# tritiled_v30_oslon.net
KiCad netlist of a schematic drawn in EAGLE
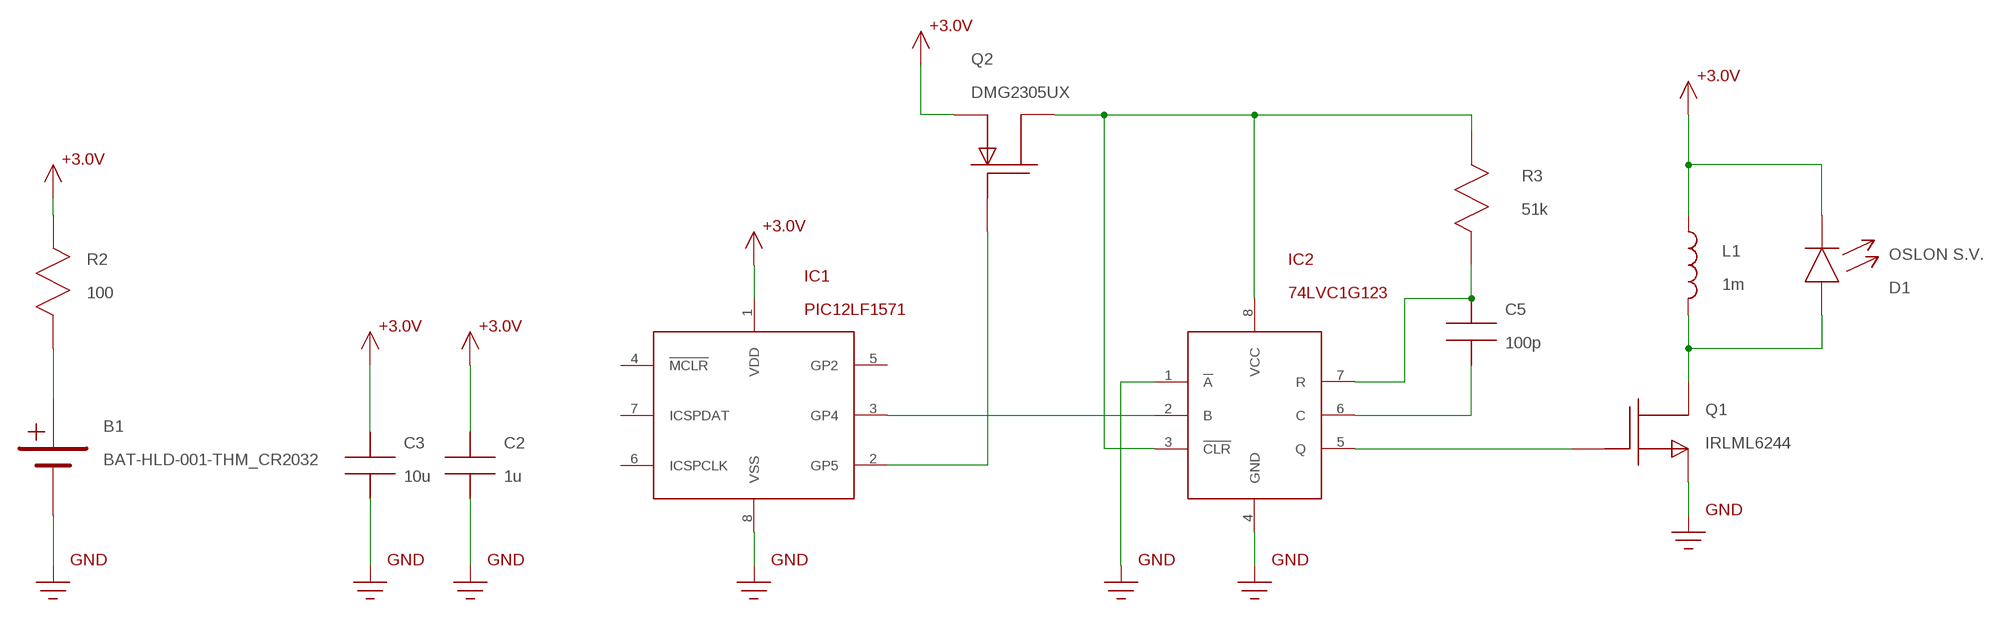
[diagram p0: schematic, sheet 1]

(export (version "E")
  (design (tool "Eeschema 10.0.6"))
  (components
    (comp (ref "B1")
      (value "BAT-HLD-001-THM_CR2032")
      (footprint "eagle-import:CR2032_BAT-HLD-001-THM")
      (libsource (lib "eagle-import") (part "BAT-HLD-001-THM_CR2032"))
    )
    (comp (ref "C2")
      (value "1u")
      (footprint "eagle-import:0805")
      (libsource (lib "eagle-import") (part "C0805"))
    )
    (comp (ref "C3")
      (value "10u")
      (footprint "eagle-import:1206")
      (libsource (lib "eagle-import") (part "C1206"))
    )
    (comp (ref "C5")
      (value "100p")
      (footprint "eagle-import:C0603")
      (libsource (lib "eagle-import") (part "C0603"))
    )
    (comp (ref "D1")
      (value "OSLON S.V.")
      (footprint "eagle-import:OSLON_3030_LED")
      (libsource (lib "eagle-import") (part "OSLON_SIGNAL"))
    )
    (comp (ref "IC1")
      (value "PIC12LF1571")
      (footprint "eagle-import:SOIC8")
      (libsource (lib "eagle-import") (part "PIC12LF1571"))
    )
    (comp (ref "IC2")
      (value "74LVC1G123")
      (footprint "eagle-import:SM8")
      (libsource (lib "eagle-import") (part "74LVC1G123"))
    )
    (comp (ref "L1")
      (value "1m")
      (footprint "eagle-import:SRR6028_INDUCTOR")
      (libsource (lib "eagle-import") (part "SRR6028_INDUCTOR"))
    )
    (comp (ref "Q1")
      (value "IRLML6244")
      (footprint "eagle-import:SOT-23")
      (libsource (lib "eagle-import") (part "ZXMN3B01FSOT23"))
    )
    (comp (ref "Q2")
      (value "DMG2305UX")
      (footprint "eagle-import:SOT-23")
      (libsource (lib "eagle-import") (part "DMG2305UXSOT23"))
    )
    (comp (ref "R2")
      (value "100")
      (footprint "eagle-import:R1206")
      (libsource (lib "eagle-import") (part "R1206"))
    )
    (comp (ref "R3")
      (value "51k")
      (footprint "eagle-import:R0603")
      (libsource (lib "eagle-import") (part "R0603"))
    )
  )
  (nets
    (net (code "1") (name "+3.0V") (class "Default")
      (node (ref "C2") (pin "P$1") (pinfunction "P$1_P$1") (pintype "bidirectional"))
      (node (ref "C3") (pin "P$1") (pinfunction "P$1_P$1") (pintype "bidirectional"))
      (node (ref "D1") (pin "C") (pinfunction "C_C") (pintype "bidirectional"))
      (node (ref "IC1") (pin "1") (pinfunction "VDD_1") (pintype "bidirectional"))
      (node (ref "L1") (pin "P$1") (pinfunction "1_P$1") (pintype "passive"))
      (node (ref "Q2") (pin "2") (pinfunction "S_2") (pintype "bidirectional"))
      (node (ref "R2") (pin "P$1") (pinfunction "P$1_P$1") (pintype "bidirectional"))
    )
    (net (code "2") (name "GND") (class "Default")
      (node (ref "B1") (pin "GND") (pinfunction "0V_GND") (pintype "power_in"))
      (node (ref "C2") (pin "P$2") (pinfunction "P$2_P$2") (pintype "bidirectional"))
      (node (ref "C3") (pin "P$2") (pinfunction "P$2_P$2") (pintype "bidirectional"))
      (node (ref "IC1") (pin "8") (pinfunction "VSS_8") (pintype "bidirectional"))
      (node (ref "IC2") (pin "1") (pinfunction "~{A}_1") (pintype "bidirectional"))
      (node (ref "IC2") (pin "4") (pinfunction "GND_4") (pintype "bidirectional"))
      (node (ref "Q1") (pin "2") (pinfunction "S_2") (pintype "bidirectional"))
    )
    (net (code "3") (name "Net-(B1-+V-Pad+V@1)") (class "Default")
      (node (ref "B1") (pin "+V@1") (pinfunction "+V_+V@1") (pintype "power_in"))
      (node (ref "B1") (pin "+V@2") (pinfunction "+V_+V@2") (pintype "power_in"))
      (node (ref "B1") (pin "+V@3") (pinfunction "+V_+V@3") (pintype "power_in"))
      (node (ref "B1") (pin "+V@4") (pinfunction "+V_+V@4") (pintype "power_in"))
      (node (ref "R2") (pin "P$2") (pinfunction "P$2_P$2") (pintype "bidirectional"))
    )
    (net (code "4") (name "Net-(IC1-GP4)") (class "Default")
      (node (ref "IC1") (pin "3") (pinfunction "GP4_3") (pintype "bidirectional"))
      (node (ref "IC2") (pin "2") (pinfunction "B_2") (pintype "bidirectional"))
    )
    (net (code "5") (name "Net-(IC1-GP5)") (class "Default")
      (node (ref "IC1") (pin "2") (pinfunction "GP5_2") (pintype "bidirectional"))
      (node (ref "Q2") (pin "1") (pinfunction "G_1") (pintype "bidirectional"))
    )
    (net (code "6") (name "Net-(IC2-C)") (class "Default")
      (node (ref "C5") (pin "P$2") (pinfunction "P$2_P$2") (pintype "bidirectional"))
      (node (ref "IC2") (pin "6") (pinfunction "C_6") (pintype "bidirectional"))
    )
    (net (code "7") (name "Net-(IC2-Q)") (class "Default")
      (node (ref "IC2") (pin "5") (pinfunction "Q_5") (pintype "bidirectional"))
      (node (ref "Q1") (pin "1") (pinfunction "G_1") (pintype "bidirectional"))
    )
    (net (code "8") (name "Net-(IC2-R)") (class "Default")
      (node (ref "C5") (pin "P$1") (pinfunction "P$1_P$1") (pintype "bidirectional"))
      (node (ref "IC2") (pin "7") (pinfunction "R_7") (pintype "bidirectional"))
      (node (ref "R3") (pin "P$1") (pinfunction "P$1_P$1") (pintype "bidirectional"))
    )
    (net (code "9") (name "Net-(IC2-VCC)") (class "Default")
      (node (ref "IC2") (pin "3") (pinfunction "~{CLR}_3") (pintype "bidirectional"))
      (node (ref "IC2") (pin "8") (pinfunction "VCC_8") (pintype "bidirectional"))
      (node (ref "Q2") (pin "3") (pinfunction "D_3") (pintype "bidirectional"))
      (node (ref "R3") (pin "P$2") (pinfunction "P$2_P$2") (pintype "bidirectional"))
    )
    (net (code "10") (name "Net-(L1-2)") (class "Default")
      (node (ref "D1") (pin "A") (pinfunction "A_A") (pintype "bidirectional"))
      (node (ref "L1") (pin "P$2") (pinfunction "2_P$2") (pintype "passive"))
      (node (ref "Q1") (pin "3") (pinfunction "D_3") (pintype "bidirectional"))
    )
    (net (code "11") (name "unconnected-(IC1-GP2-Pad5)") (class "Default")
      (node (ref "IC1") (pin "5") (pinfunction "GP2_5") (pintype "bidirectional"))
    )
    (net (code "12") (name "unconnected-(IC1-ICSPCLK-Pad6)") (class "Default")
      (node (ref "IC1") (pin "6") (pinfunction "ICSPCLK_6") (pintype "bidirectional"))
    )
    (net (code "13") (name "unconnected-(IC1-ICSPDAT-Pad7)") (class "Default")
      (node (ref "IC1") (pin "7") (pinfunction "ICSPDAT_7") (pintype "bidirectional"))
    )
    (net (code "14") (name "unconnected-(IC1-~{MCLR}-Pad4)") (class "Default")
      (node (ref "IC1") (pin "4") (pinfunction "~{MCLR}_4") (pintype "bidirectional"))
    )
  )
)
